# power_disrtibution.net
KiCad netlist of a schematic drawn in EAGLE
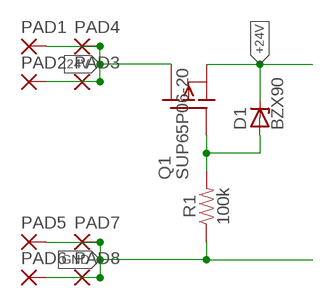
[diagram p0: schematic, sheet 1]

(export (version "E")
  (design (tool "Eeschema 10.0.6"))
  (components
    (comp (ref "D1")
      (value "BZX90")
      (footprint "eagle-import:DO34Z7")
      (libsource (lib "eagle-import") (part "BZX90"))
    )
    (comp (ref "PAD1")
      (value "SMD5")
      (footprint "eagle-import:SMD2,54-5,08")
      (libsource (lib "eagle-import") (part "SMD5"))
    )
    (comp (ref "PAD2")
      (value "SMD5")
      (footprint "eagle-import:SMD2,54-5,08")
      (libsource (lib "eagle-import") (part "SMD5"))
    )
    (comp (ref "PAD3")
      (value "SMD5")
      (footprint "eagle-import:SMD2,54-5,08")
      (libsource (lib "eagle-import") (part "SMD5"))
    )
    (comp (ref "PAD4")
      (value "SMD5")
      (footprint "eagle-import:SMD2,54-5,08")
      (libsource (lib "eagle-import") (part "SMD5"))
    )
    (comp (ref "PAD5")
      (value "SMD5")
      (footprint "eagle-import:SMD2,54-5,08")
      (libsource (lib "eagle-import") (part "SMD5"))
    )
    (comp (ref "PAD6")
      (value "SMD5")
      (footprint "eagle-import:SMD2,54-5,08")
      (libsource (lib "eagle-import") (part "SMD5"))
    )
    (comp (ref "PAD7")
      (value "SMD5")
      (footprint "eagle-import:SMD2,54-5,08")
      (libsource (lib "eagle-import") (part "SMD5"))
    )
    (comp (ref "PAD8")
      (value "SMD5")
      (footprint "eagle-import:SMD2,54-5,08")
      (libsource (lib "eagle-import") (part "SMD5"))
    )
    (comp (ref "Q1")
      (value "SUP65P06-20")
      (footprint "eagle-import:TO220")
      (libsource (lib "eagle-import") (part "SUP65P06-20"))
    )
    (comp (ref "R1")
      (value "100k")
      (footprint "eagle-import:AXIAL-0.3")
      (libsource (lib "eagle-import") (part "100KOHM-HORIZ-1/4W-5%"))
    )
  )
  (nets
    (net (code "1") (name "+24V") (class "Default")
      (node (ref "D1") (pin "C") (pinfunction "C_C") (pintype "passive"))
      (node (ref "Q1") (pin "3") (pinfunction "S_3") (pintype "passive"))
    )
    (net (code "2") (name "24V") (class "Default")
      (node (ref "PAD1") (pin "1") (pinfunction "P_1") (pintype "passive"))
      (node (ref "PAD2") (pin "1") (pinfunction "P_1") (pintype "passive"))
      (node (ref "PAD3") (pin "1") (pinfunction "P_1") (pintype "passive"))
      (node (ref "PAD4") (pin "1") (pinfunction "P_1") (pintype "passive"))
      (node (ref "Q1") (pin "2") (pinfunction "D_2") (pintype "passive"))
    )
    (net (code "3") (name "GND") (class "Default")
      (node (ref "PAD5") (pin "1") (pinfunction "P_1") (pintype "passive"))
      (node (ref "PAD6") (pin "1") (pinfunction "P_1") (pintype "passive"))
      (node (ref "PAD7") (pin "1") (pinfunction "P_1") (pintype "passive"))
      (node (ref "PAD8") (pin "1") (pinfunction "P_1") (pintype "passive"))
      (node (ref "R1") (pin "P$1") (pinfunction "1_P$1") (pintype "passive"))
    )
    (net (code "4") (name "Net-(Q1-G)") (class "Default")
      (node (ref "D1") (pin "A") (pinfunction "A_A") (pintype "passive"))
      (node (ref "Q1") (pin "1") (pinfunction "G_1") (pintype "passive"))
      (node (ref "R1") (pin "P$2") (pinfunction "2_P$2") (pintype "passive"))
    )
  )
)
